# AirU_v2_2.net
KiCad netlist of a schematic drawn in EAGLE
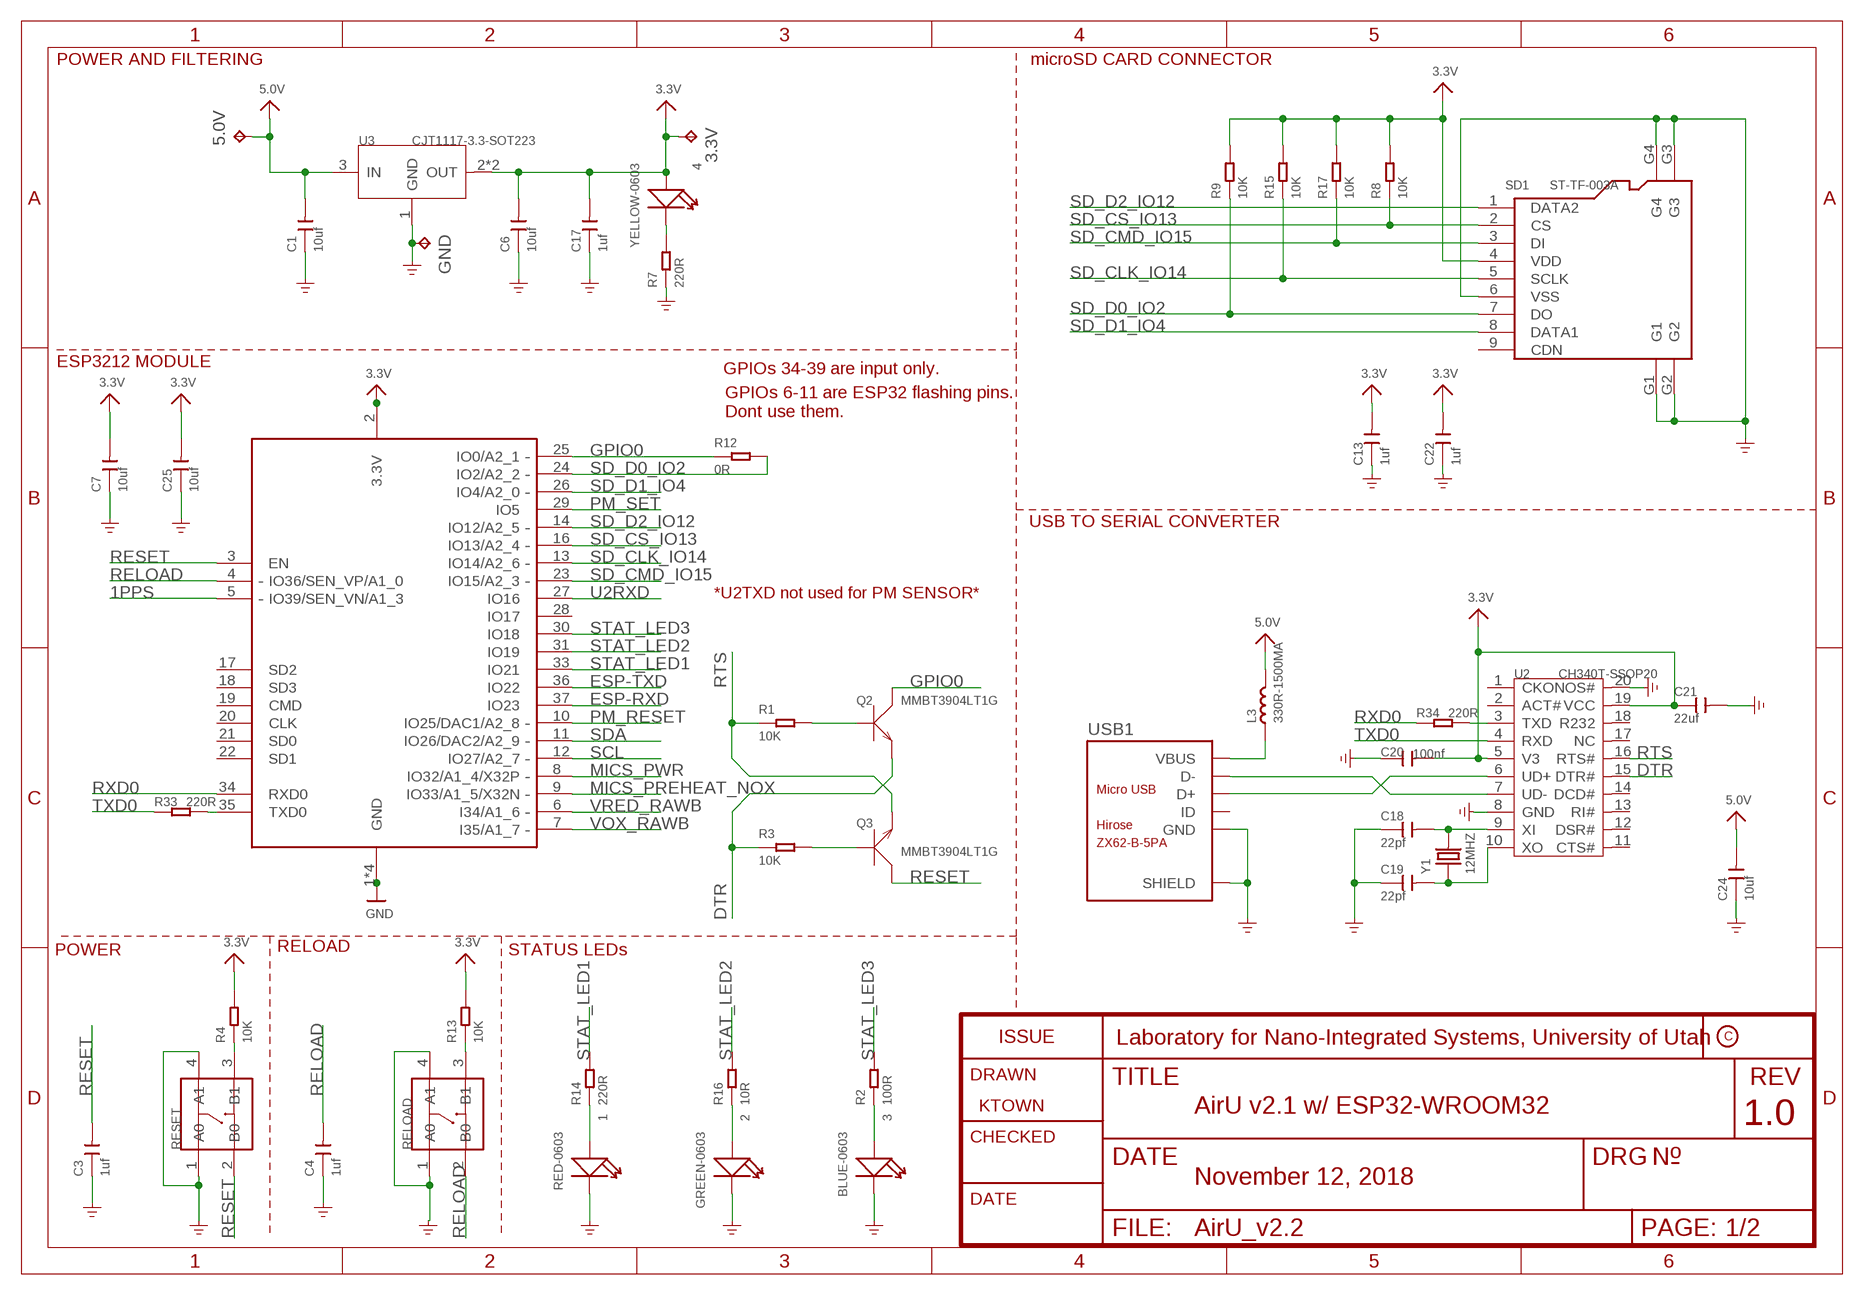
[diagram p0: schematic, sheet 1]
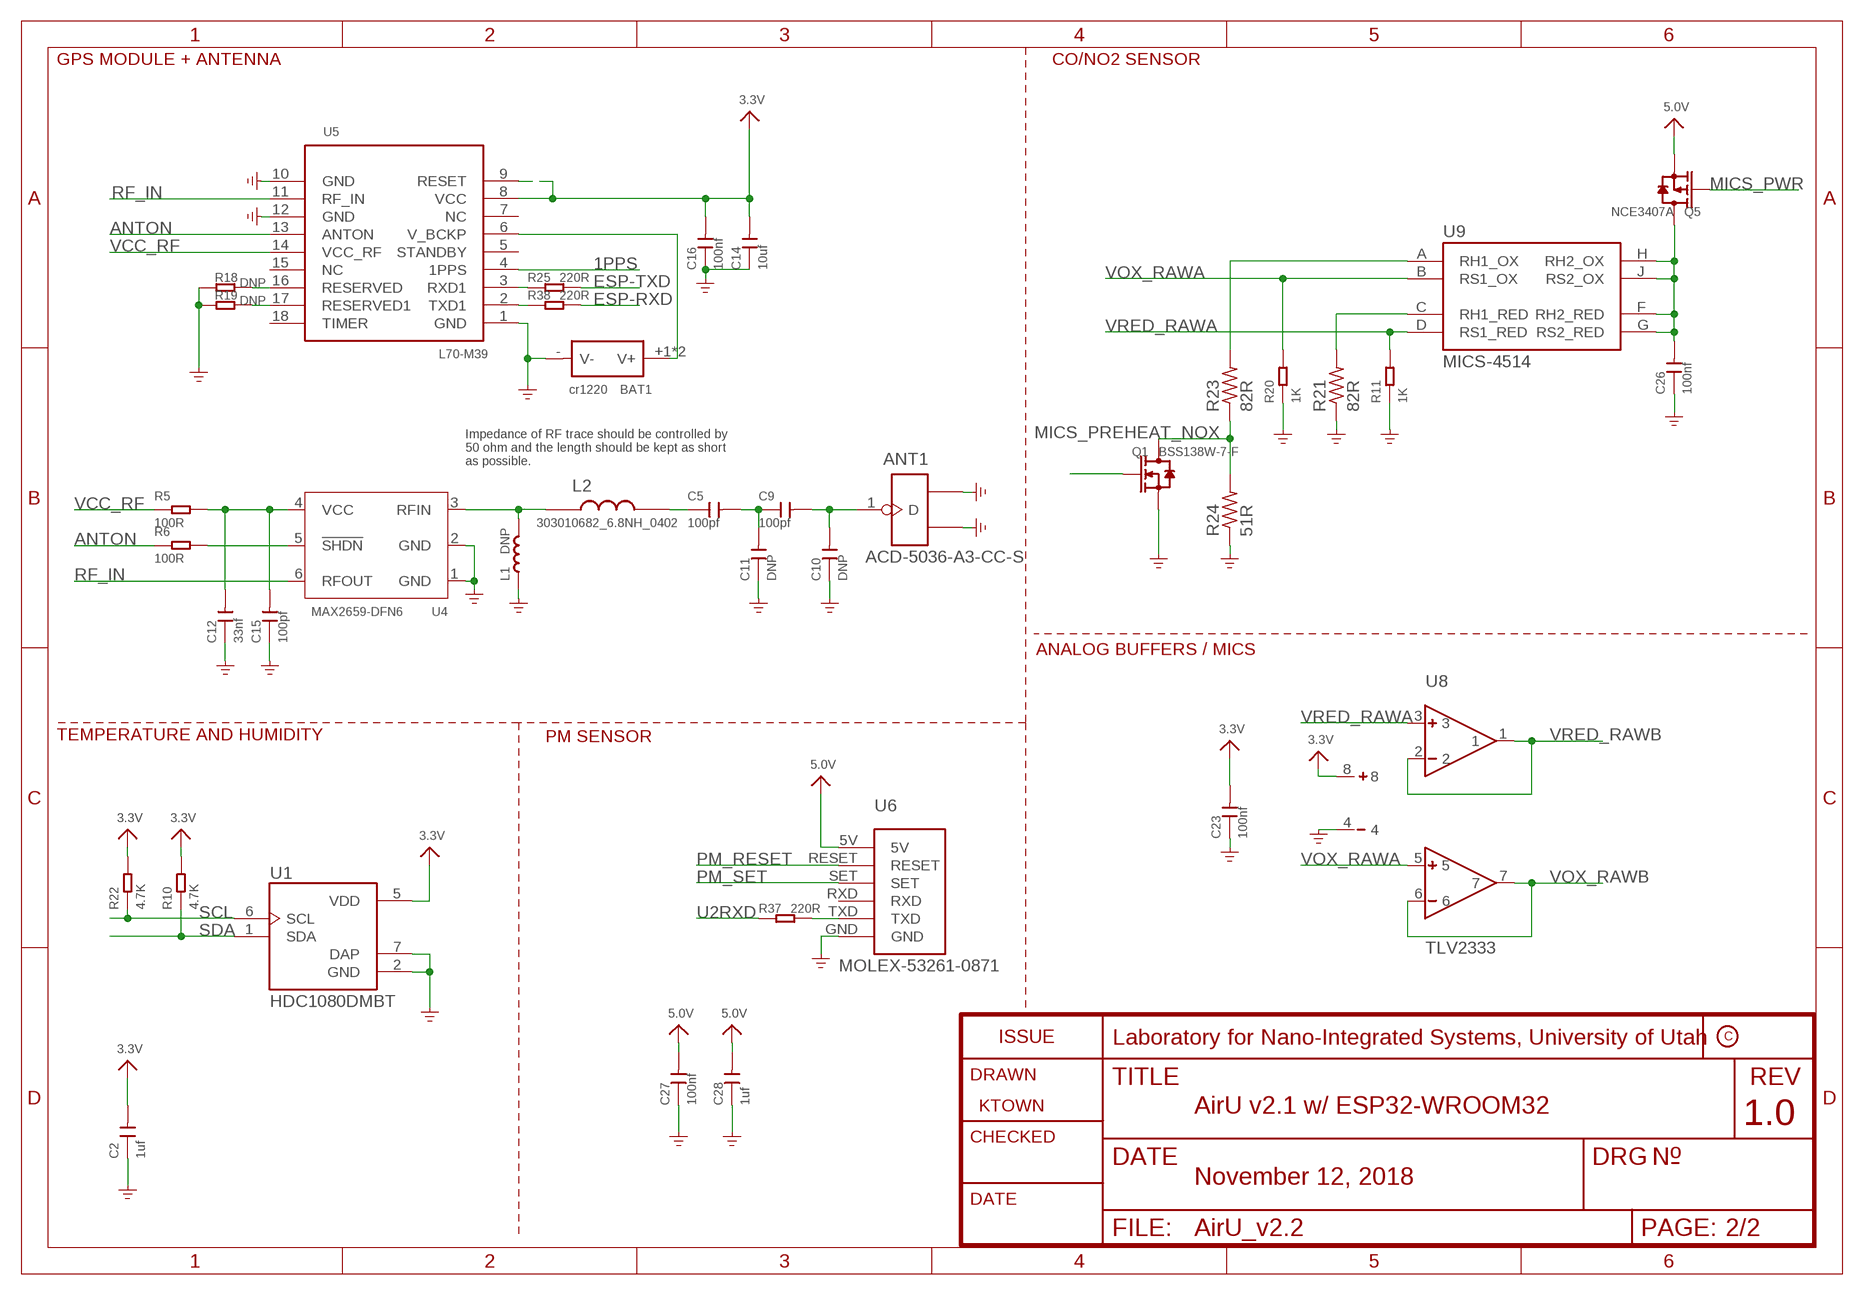
[diagram p1: schematic, sheet 2]

(export (version "E")
  (design (tool "Eeschema 10.0.6"))
  (components
    (comp (ref "1")
      (value "RED-0603")
      (footprint "eagle-import:LED-0603")
      (fields (field (name "MPN") "19-217-R6C-AL1M2VY-3T"))
      (libsource (lib "eagle-import") (part "LED-SMD-RED-DIFFUSED(0603)"))
    )
    (comp (ref "2")
      (value "GREEN-0603")
      (footprint "eagle-import:LED-0603")
      (fields (field (name "MPN") "19-217-G7C-AN1P2-3T"))
      (libsource (lib "eagle-import") (part "SMD-LED-CLEAR-GREEN(0603)"))
    )
    (comp (ref "3")
      (value "BLUE-0603")
      (footprint "eagle-import:LED-0603")
      (fields (field (name "MPN") "19-217-BHC-ZL1M2RY-3T"))
      (libsource (lib "eagle-import") (part "SMD-LED-CLEAR-BLUE(0603)"))
    )
    (comp (ref "3.3V")
      (value "TPTP20SQ")
      (footprint "eagle-import:TP20SQ")
      (libsource (lib "eagle-import") (part "TPTP20SQ"))
    )
    (comp (ref "4")
      (value "YELLOW-0603")
      (footprint "eagle-import:LED-0603")
      (fields (field (name "MPN") "19-217-Y5C-AM1N1VY-3T"))
      (libsource (lib "eagle-import") (part "SMD-LED-CLEAR-YELLOW(0603)"))
    )
    (comp (ref "5.0V")
      (value "TPTP20SQ")
      (footprint "eagle-import:TP20SQ")
      (libsource (lib "eagle-import") (part "TPTP20SQ"))
    )
    (comp (ref "C1")
      (value "10uf")
      (footprint "eagle-import:C0603")
      (fields (field (name "MPN") "CC0603KRX5R6BB106"))
      (libsource (lib "eagle-import") (part "CERAMIC-10UF-10V-10%-X5R(0603)"))
    )
    (comp (ref "C3")
      (value "1uf")
      (footprint "eagle-import:C0603")
      (fields (field (name "MPN") "CC0603KRX7R8BB105"))
      (libsource (lib "eagle-import") (part "CERAMIC-1UF-25V-10%-X7R(0603)"))
    )
    (comp (ref "C4")
      (value "1uf")
      (footprint "eagle-import:C0603")
      (fields (field (name "MPN") "CC0603KRX7R8BB105"))
      (libsource (lib "eagle-import") (part "CERAMIC-1UF-25V-10%-X7R(0603)"))
    )
    (comp (ref "C6")
      (value "10uf")
      (footprint "eagle-import:C0603")
      (fields (field (name "MPN") "CC0603KRX5R6BB106"))
      (libsource (lib "eagle-import") (part "CERAMIC-10UF-10V-10%-X5R(0603)"))
    )
    (comp (ref "C7")
      (value "10uf")
      (footprint "eagle-import:C0603")
      (fields (field (name "MPN") "CC0603KRX5R6BB106"))
      (libsource (lib "eagle-import") (part "CERAMIC-10UF-10V-10%-X5R(0603)"))
    )
    (comp (ref "C13")
      (value "1uf")
      (footprint "eagle-import:C0603")
      (fields (field (name "MPN") "CC0603KRX7R8BB105"))
      (libsource (lib "eagle-import") (part "CERAMIC-1UF-25V-10%-X7R(0603)"))
    )
    (comp (ref "C17")
      (value "1uf")
      (footprint "eagle-import:C0603")
      (fields (field (name "MPN") "CC0603KRX7R8BB105"))
      (libsource (lib "eagle-import") (part "CERAMIC-1UF-25V-10%-X7R(0603)"))
    )
    (comp (ref "C18")
      (value "22pf")
      (footprint "eagle-import:C0603")
      (fields (field (name "MPN") "CC0603JRNPO9BN220"))
      (libsource (lib "eagle-import") (part "CERAMIC-22PF-50V-5%-NPO(0603)"))
    )
    (comp (ref "C19")
      (value "22pf")
      (footprint "eagle-import:C0603")
      (fields (field (name "MPN") "CC0603JRNPO9BN220"))
      (libsource (lib "eagle-import") (part "CERAMIC-22PF-50V-5%-NPO(0603)"))
    )
    (comp (ref "C20")
      (value "100nf")
      (footprint "eagle-import:C0603")
      (fields (field (name "MPN") "CC0603KRX7R9BB104"))
      (libsource (lib "eagle-import") (part "CERAMIC-100NF-50V-10%-X7R(0603)"))
    )
    (comp (ref "C21")
      (value "22uf")
      (footprint "eagle-import:C0805")
      (fields (field (name "MPN") "CC0805MKX5R5BB226"))
      (libsource (lib "eagle-import") (part "CERAMIC-22UF-6.3V-20%-X5R(0805)"))
    )
    (comp (ref "C22")
      (value "1uf")
      (footprint "eagle-import:C0603")
      (fields (field (name "MPN") "CC0603KRX7R8BB105"))
      (libsource (lib "eagle-import") (part "CERAMIC-1UF-25V-10%-X7R(0603)"))
    )
    (comp (ref "C24")
      (value "10uf")
      (footprint "eagle-import:C0603")
      (fields (field (name "MPN") "CC0603KRX5R6BB106"))
      (libsource (lib "eagle-import") (part "CERAMIC-10UF-10V-10%-X5R(0603)"))
    )
    (comp (ref "C25")
      (value "10uf")
      (footprint "eagle-import:C0603")
      (fields (field (name "MPN") "CC0603KRX5R6BB106"))
      (libsource (lib "eagle-import") (part "CERAMIC-10UF-10V-10%-X5R(0603)"))
    )
    (comp (ref "GND")
      (value "TPTP20SQ")
      (footprint "eagle-import:TP20SQ")
      (libsource (lib "eagle-import") (part "TPTP20SQ"))
    )
    (comp (ref "L3")
      (value "330R-1500MA")
      (footprint "eagle-import:L0805")
      (fields (field (name "MPN") "BLM21PG331SN1D"))
      (libsource (lib "eagle-import") (part "SMD-FERRITE-BEAD-330R-1500MA(0805)'0805'"))
    )
    (comp (ref "Q2")
      (value "MMBT3904LT1G")
      (footprint "eagle-import:SOT-23")
      (libsource (lib "eagle-import") (part "SMD-TRANSISTORS-NPN-40V-200MA-MMBT3904LT1G(SOT-23)"))
    )
    (comp (ref "Q3")
      (value "MMBT3904LT1G")
      (footprint "eagle-import:SOT-23")
      (libsource (lib "eagle-import") (part "SMD-TRANSISTORS-NPN-40V-200MA-MMBT3904LT1G(SOT-23)"))
    )
    (comp (ref "R1")
      (value "10K")
      (footprint "eagle-import:R0603")
      (fields (field (name "MPN") "RC0603FR-0710KL"))
      (libsource (lib "eagle-import") (part "SMD-RES-10K-1%-1/10W(0603)"))
    )
    (comp (ref "R2")
      (value "100R")
      (footprint "eagle-import:R0603")
      (fields (field (name "MPN") "RC0603JR-07100RL"))
      (libsource (lib "eagle-import") (part "SMD-RES-100R-5%-1/10W(0603)"))
    )
    (comp (ref "R3")
      (value "10K")
      (footprint "eagle-import:R0603")
      (fields (field (name "MPN") "RC0603FR-0710KL"))
      (libsource (lib "eagle-import") (part "SMD-RES-10K-1%-1/10W(0603)"))
    )
    (comp (ref "R4")
      (value "10K")
      (footprint "eagle-import:R0603")
      (fields (field (name "MPN") "RC0603FR-0710KL"))
      (libsource (lib "eagle-import") (part "SMD-RES-10K-1%-1/10W(0603)"))
    )
    (comp (ref "R7")
      (value "220R")
      (footprint "eagle-import:R0603")
      (fields (field (name "MPN") "RC0603JR-07220RL"))
      (libsource (lib "eagle-import") (part "SMD-RES-220R-5%-1/10W(0603)"))
    )
    (comp (ref "R8")
      (value "10K")
      (footprint "eagle-import:R0603")
      (fields (field (name "MPN") "RC0603FR-0710KL"))
      (libsource (lib "eagle-import") (part "SMD-RES-10K-1%-1/10W(0603)"))
    )
    (comp (ref "R9")
      (value "10K")
      (footprint "eagle-import:R0603")
      (fields (field (name "MPN") "RC0603FR-0710KL"))
      (libsource (lib "eagle-import") (part "SMD-RES-10K-1%-1/10W(0603)"))
    )
    (comp (ref "R12")
      (value "0R")
      (footprint "eagle-import:R0603")
      (fields (field (name "MPN") "RC0603JR-070RL"))
      (libsource (lib "eagle-import") (part "SMD-RES-0R-5%-1/10W(0603)"))
    )
    (comp (ref "R13")
      (value "10K")
      (footprint "eagle-import:R0603")
      (fields (field (name "MPN") "RC0603FR-0710KL"))
      (libsource (lib "eagle-import") (part "SMD-RES-10K-1%-1/10W(0603)"))
    )
    (comp (ref "R14")
      (value "220R")
      (footprint "eagle-import:R0603")
      (fields (field (name "MPN") "RC0603JR-07220RL"))
      (libsource (lib "eagle-import") (part "SMD-RES-220R-5%-1/10W(0603)"))
    )
    (comp (ref "R15")
      (value "10K")
      (footprint "eagle-import:R0603")
      (fields (field (name "MPN") "RC0603FR-0710KL"))
      (libsource (lib "eagle-import") (part "SMD-RES-10K-1%-1/10W(0603)"))
    )
    (comp (ref "R16")
      (value "10R")
      (footprint "eagle-import:R0603")
      (fields (field (name "MPN") "RC0603JR-0710RL"))
      (libsource (lib "eagle-import") (part "SMD-RES-10R-5%-1/10W(0603)"))
    )
    (comp (ref "R17")
      (value "10K")
      (footprint "eagle-import:R0603")
      (fields (field (name "MPN") "RC0603FR-0710KL"))
      (libsource (lib "eagle-import") (part "SMD-RES-10K-1%-1/10W(0603)"))
    )
    (comp (ref "R33")
      (value "220R")
      (footprint "eagle-import:R0603")
      (fields (field (name "MPN") "RC0603JR-07220RL"))
      (libsource (lib "eagle-import") (part "SMD-RES-220R-5%-1/10W(0603)"))
    )
    (comp (ref "R34")
      (value "220R")
      (footprint "eagle-import:R0603")
      (fields (field (name "MPN") "RC0603JR-07220RL"))
      (libsource (lib "eagle-import") (part "SMD-RES-220R-5%-1/10W(0603)"))
    )
    (comp (ref "RELOAD")
      (value "DIP-SWITCH-TACTILE-SPST-NO/TS-1109(4P-D6.0MM)'TS-1109'")
      (footprint "eagle-import:SW4-6.0X6.0X5.0MM")
      (libsource (lib "eagle-import") (part "DIP-SWITCH-TACTILE-SPST-NO/TS-1109(4P-D6.0MM)'TS-1109'"))
    )
    (comp (ref "RESET")
      (value "DIP-SWITCH-TACTILE-SPST-NO/TS-1109(4P-D6.0MM)'TS-1109'")
      (footprint "eagle-import:SW4-6.0X6.0X5.0MM")
      (libsource (lib "eagle-import") (part "DIP-SWITCH-TACTILE-SPST-NO/TS-1109(4P-D6.0MM)'TS-1109'"))
    )
    (comp (ref "SD1")
      (value "ST-TF-003A")
      (footprint "eagle-import:MICRO-SD9+4P-SMD-16.1X14.5X1.85MM")
      (libsource (lib "eagle-import") (part "MICRO-SD-CARD-SOCKET-9P(ST-TF-003A)"))
    )
    (comp (ref "U2")
      (value "CH340T-SSOP20")
      (footprint "eagle-import:SSOP20-0.65-7.6X5.2MM")
      (fields (field (name "MPN") "CH340T"))
      (libsource (lib "eagle-import") (part "INTERFACE-CH340T(SSOP20)"))
    )
    (comp (ref "U3")
      (value "CJT1117-3.3-SOT223")
      (footprint "eagle-import:SOT-223")
      (fields (field (name "MPN") "CJT1117-3.3"))
      (libsource (lib "eagle-import") (part "PMIC-CJT1117-3.3(SOT223)"))
    )
    (comp (ref "U7")
      (value "ESP32_WROOM32_SKINNY")
      (footprint "eagle-import:WROOM32_SKINNY")
      (libsource (lib "eagle-import") (part "ESP32_WROOM32_SKINNY"))
    )
    (comp (ref "USB1")
      (value "ZX62-B-5PA")
      (footprint "eagle-import:MICRO-USB5+6P-SMD-0.65-AB")
      (libsource (lib "eagle-import") (part "MICRO-USB-SMD(ZX62-B-5PA)"))
    )
    (comp (ref "Y1")
      (value "12MHZ")
      (footprint "eagle-import:X2-SMD-5.0X3.2X1.3MM")
      (fields (field (name "MPN") "5032/2P"))
      (libsource (lib "eagle-import") (part "SMD-CRYSTAL-12MHZ-20PF-20PPM-40R(2P-5.0X3.2MM)"))
    )
    (comp (ref "ANT1")
      (value "ACD-5036-A3-CC-S")
      (footprint "eagle-import:ANT3-SMD-5.2X3.7X0.7MM")
      (libsource (lib "eagle-import") (part "ANTENNA-ACD5036"))
    )
    (comp (ref "BAT1")
      (value "cr1220")
      (footprint "eagle-import:BAT2P-13.5-CR1220")
      (libsource (lib "eagle-import") (part "DIP-BATTERY-CELL-HOLDER(1220)"))
    )
    (comp (ref "C2")
      (value "1uf")
      (footprint "eagle-import:C0603")
      (fields (field (name "MPN") "CC0603KRX7R8BB105"))
      (libsource (lib "eagle-import") (part "CERAMIC-1UF-25V-10%-X7R(0603)"))
    )
    (comp (ref "C5")
      (value "100pf")
      (footprint "eagle-import:C0603")
      (fields (field (name "MPN") "CC0603JRNPO9BN101"))
      (libsource (lib "eagle-import") (part "CERAMIC-100PF-50V-5%-NPO(0603)"))
    )
    (comp (ref "C9")
      (value "100pf")
      (footprint "eagle-import:C0603")
      (fields (field (name "MPN") "CC0603JRNPO9BN101"))
      (libsource (lib "eagle-import") (part "CERAMIC-100PF-50V-5%-NPO(0603)"))
    )
    (comp (ref "C10")
      (value "DNP")
      (footprint "eagle-import:C0603")
      (fields (field (name "MPN") "CC0603JRNPO9BN101"))
      (libsource (lib "eagle-import") (part "CERAMIC-100PF-50V-5%-NPO(0603)"))
    )
    (comp (ref "C11")
      (value "DNP")
      (footprint "eagle-import:C0603")
      (fields (field (name "MPN") "CC0603JRNPO9BN101"))
      (libsource (lib "eagle-import") (part "CERAMIC-100PF-50V-5%-NPO(0603)"))
    )
    (comp (ref "C12")
      (value "33nf")
      (footprint "eagle-import:C0603")
      (fields (field (name "MPN") "CC0603KRX7R9BB333"))
      (libsource (lib "eagle-import") (part "CERAMIC-33NF-50V-10%-X7R(0603)"))
    )
    (comp (ref "C14")
      (value "10uf")
      (footprint "eagle-import:C0603")
      (fields (field (name "MPN") "CC0603KRX5R6BB106"))
      (libsource (lib "eagle-import") (part "CERAMIC-10UF-10V-10%-X5R(0603)"))
    )
    (comp (ref "C15")
      (value "100pf")
      (footprint "eagle-import:C0603")
      (fields (field (name "MPN") "CC0603JRNPO9BN101"))
      (libsource (lib "eagle-import") (part "CERAMIC-100PF-50V-5%-NPO(0603)"))
    )
    (comp (ref "C16")
      (value "100nf")
      (footprint "eagle-import:C0603")
      (fields (field (name "MPN") "CC0603KRX7R9BB104"))
      (libsource (lib "eagle-import") (part "CERAMIC-100NF-50V-10%-X7R(0603)"))
    )
    (comp (ref "C23")
      (value "100nf")
      (footprint "eagle-import:C0603")
      (fields (field (name "MPN") "CC0603KRX7R9BB104"))
      (libsource (lib "eagle-import") (part "CERAMIC-100NF-50V-10%-X7R(0603)"))
    )
    (comp (ref "C26")
      (value "100nf")
      (footprint "eagle-import:C0603")
      (fields (field (name "MPN") "CC0603KRX7R9BB104"))
      (libsource (lib "eagle-import") (part "CERAMIC-100NF-50V-10%-X7R(0603)"))
    )
    (comp (ref "C27")
      (value "100nf")
      (footprint "eagle-import:C0603")
      (fields (field (name "MPN") "CC0603KRX7R9BB104"))
      (libsource (lib "eagle-import") (part "CERAMIC-100NF-50V-10%-X7R(0603)"))
    )
    (comp (ref "C28")
      (value "1uf")
      (footprint "eagle-import:C0603")
      (fields (field (name "MPN") "CC0603KRX7R8BB105"))
      (libsource (lib "eagle-import") (part "CERAMIC-1UF-25V-10%-X7R(0603)"))
    )
    (comp (ref "L1")
      (value "DNP")
      (footprint "eagle-import:L0201")
      (libsource (lib "eagle-import") (part "INDUCTOR/FERRITE-BEAD-0201"))
    )
    (comp (ref "L2")
      (value "303010682_6.8NH_0402")
      (footprint "eagle-import:L0402")
      (libsource (lib "eagle-import") (part "303010682_6.8NH_0402"))
    )
    (comp (ref "Q1")
      (value "BSS138W-7-F")
      (footprint "eagle-import:SOT-23")
      (libsource (lib "eagle-import") (part "SMD-MOSFET-N-CH-50V-200MA-BSS138W-7-F(SOT-23)"))
    )
    (comp (ref "Q5")
      (value "NCE3407A")
      (footprint "eagle-import:SOT-23")
      (libsource (lib "eagle-import") (part "SMD-MOSFET-P-CH-VDC=30V-ID=4.3A-NCE3407A(SOT-23)"))
    )
    (comp (ref "R5")
      (value "100R")
      (footprint "eagle-import:R0603")
      (fields (field (name "MPN") "RC0603JR-07100RL"))
      (libsource (lib "eagle-import") (part "SMD-RES-100R-5%-1/10W(0603)"))
    )
    (comp (ref "R6")
      (value "100R")
      (footprint "eagle-import:R0603")
      (fields (field (name "MPN") "RC0603JR-07100RL"))
      (libsource (lib "eagle-import") (part "SMD-RES-100R-5%-1/10W(0603)"))
    )
    (comp (ref "R10")
      (value "4.7K")
      (footprint "eagle-import:R0603")
      (fields (field (name "MPN") "RC0603JR-074K7L"))
      (libsource (lib "eagle-import") (part "SMD-RES-4.7K-5%-1/10W(0603)"))
    )
    (comp (ref "R11")
      (value "1K")
      (footprint "eagle-import:R0603")
      (fields (field (name "MPN") "RC0603FR-071KL"))
      (libsource (lib "eagle-import") (part "SMD-RES-1K-1%-1/10W(0603)"))
    )
    (comp (ref "R18")
      (value "DNP")
      (footprint "eagle-import:R0603")
      (fields (field (name "MPN") "RC0603FR-0710KL"))
      (libsource (lib "eagle-import") (part "SMD-RES-10K-1%-1/10W(0603)"))
    )
    (comp (ref "R19")
      (value "DNP")
      (footprint "eagle-import:R0603")
      (fields (field (name "MPN") "RC0603FR-0710KL"))
      (libsource (lib "eagle-import") (part "SMD-RES-10K-1%-1/10W(0603)"))
    )
    (comp (ref "R20")
      (value "1K")
      (footprint "eagle-import:R0603")
      (fields (field (name "MPN") "RC0603FR-071KL"))
      (libsource (lib "eagle-import") (part "SMD-RES-1K-1%-1/10W(0603)"))
    )
    (comp (ref "R21")
      (value "82R")
      (footprint "eagle-import:R0603")
      (libsource (lib "eagle-import") (part "R-US_R0603"))
    )
    (comp (ref "R22")
      (value "4.7K")
      (footprint "eagle-import:R0603")
      (fields (field (name "MPN") "RC0603JR-074K7L"))
      (libsource (lib "eagle-import") (part "SMD-RES-4.7K-5%-1/10W(0603)"))
    )
    (comp (ref "R23")
      (value "82R")
      (footprint "eagle-import:R0603")
      (libsource (lib "eagle-import") (part "R-US_R0603"))
    )
    (comp (ref "R24")
      (value "51R")
      (footprint "eagle-import:R0603")
      (libsource (lib "eagle-import") (part "R-US_R0603"))
    )
    (comp (ref "R25")
      (value "220R")
      (footprint "eagle-import:R0603")
      (fields (field (name "MPN") "RC0603JR-07220RL"))
      (libsource (lib "eagle-import") (part "SMD-RES-220R-5%-1/10W(0603)"))
    )
    (comp (ref "R37")
      (value "220R")
      (footprint "eagle-import:R0603")
      (fields (field (name "MPN") "RC0603JR-07220RL"))
      (libsource (lib "eagle-import") (part "SMD-RES-220R-5%-1/10W(0603)"))
    )
    (comp (ref "R38")
      (value "220R")
      (footprint "eagle-import:R0603")
      (fields (field (name "MPN") "RC0603JR-07220RL"))
      (libsource (lib "eagle-import") (part "SMD-RES-220R-5%-1/10W(0603)"))
    )
    (comp (ref "U1")
      (value "HDC1080DMBT")
      (footprint "eagle-import:SON100P300X300X80-7N")
      (fields (field (name "DIGI-KEY_PART_NUMBER") "296-43864-1-ND") (field (name "MF") "Texas Instruments"))
      (libsource (lib "eagle-import") (part "HDC1080DMBT"))
    )
    (comp (ref "U4")
      (value "MAX2659-DFN6")
      (footprint "eagle-import:DFN6-0.5-1.5X1.2X0.72MM")
      (fields (field (name "MPN") "MAX2659"))
      (libsource (lib "eagle-import") (part "AMPLIFIER-MAX2659"))
    )
    (comp (ref "U5")
      (value "L70-M39")
      (footprint "eagle-import:LGA18-1.1-9.7X10.1X2.5MM")
      (fields (field (name "MPN") "L70"))
      (libsource (lib "eagle-import") (part "MOUDLE-GPS-L70-HARDWARE"))
    )
    (comp (ref "U6")
      (value "MOLEX-53261-0871")
      (footprint "eagle-import:MOLEX-53261-0871")
      (libsource (lib "eagle-import") (part "MOLEX-53261-0871"))
    )
    (comp (ref "U8")
      (value "TLV2333")
      (footprint "eagle-import:TLV2333")
      (libsource (lib "eagle-import") (part "TLV2333"))
    )
    (comp (ref "U9")
      (value "MICS-4514")
      (footprint "eagle-import:MICS_10-SMD")
      (fields (field (name "MF") "Amphenol"))
      (libsource (lib "eagle-import") (part "MICS-4514"))
    )
  )
  (nets
    (net (code "1") (name "1PPS") (class "Default")
      (node (ref "U5") (pin "4") (pinfunction "1PPS_4") (pintype "bidirectional"))
      (node (ref "U7") (pin "5") (pinfunction "IO39/SEN_VN/A1_3_5") (pintype "passive"))
    )
    (net (code "2") (name "3.3V") (class "Default")
      (node (ref "3.3V") (pin "TP") (pinfunction "TP_TP") (pintype "input"))
      (node (ref "4") (pin "+") (pinfunction "+_+") (pintype "passive"))
      (node (ref "C13") (pin "2") (pinfunction "2_2") (pintype "passive"))
      (node (ref "C14") (pin "2") (pinfunction "2_2") (pintype "passive"))
      (node (ref "C16") (pin "2") (pinfunction "2_2") (pintype "passive"))
      (node (ref "C17") (pin "2") (pinfunction "2_2") (pintype "passive"))
      (node (ref "C2") (pin "2") (pinfunction "2_2") (pintype "passive"))
      (node (ref "C20") (pin "2") (pinfunction "2_2") (pintype "passive"))
      (node (ref "C21") (pin "1") (pinfunction "1_1") (pintype "passive"))
      (node (ref "C22") (pin "2") (pinfunction "2_2") (pintype "passive"))
      (node (ref "C23") (pin "2") (pinfunction "2_2") (pintype "passive"))
      (node (ref "C25") (pin "2") (pinfunction "2_2") (pintype "passive"))
      (node (ref "C6") (pin "2") (pinfunction "2_2") (pintype "passive"))
      (node (ref "C7") (pin "2") (pinfunction "2_2") (pintype "passive"))
      (node (ref "R10") (pin "2") (pinfunction "2_2") (pintype "passive"))
      (node (ref "R13") (pin "2") (pinfunction "2_2") (pintype "passive"))
      (node (ref "R15") (pin "2") (pinfunction "2_2") (pintype "passive"))
      (node (ref "R17") (pin "2") (pinfunction "2_2") (pintype "passive"))
      (node (ref "R22") (pin "2") (pinfunction "2_2") (pintype "passive"))
      (node (ref "R4") (pin "2") (pinfunction "2_2") (pintype "passive"))
      (node (ref "R8") (pin "2") (pinfunction "2_2") (pintype "passive"))
      (node (ref "R9") (pin "2") (pinfunction "2_2") (pintype "passive"))
      (node (ref "SD1") (pin "4") (pinfunction "VDD_4") (pintype "bidirectional"))
      (node (ref "U1") (pin "5") (pinfunction "VDD_5") (pintype "power_in"))
      (node (ref "U2") (pin "19") (pinfunction "VCC_19") (pintype "power_in"))
      (node (ref "U2") (pin "5") (pinfunction "V3_5") (pintype "power_in"))
      (node (ref "U3") (pin "2") (pinfunction "OUT_2") (pintype "bidirectional"))
      (node (ref "U3") (pin "TER") (pinfunction "OUT_TER") (pintype "bidirectional"))
      (node (ref "U5") (pin "8") (pinfunction "VCC_8") (pintype "power_in"))
      (node (ref "U5") (pin "9") (pinfunction "RESET_9") (pintype "bidirectional"))
      (node (ref "U7") (pin "2") (pinfunction "3.3V_2") (pintype "passive"))
      (node (ref "U8") (pin "8") (pinfunction "8_8") (pintype "bidirectional"))
    )
    (net (code "3") (name "5.0V") (class "Default")
      (node (ref "5.0V") (pin "TP") (pinfunction "TP_TP") (pintype "input"))
      (node (ref "C1") (pin "2") (pinfunction "2_2") (pintype "passive"))
      (node (ref "C24") (pin "2") (pinfunction "2_2") (pintype "passive"))
      (node (ref "C27") (pin "2") (pinfunction "2_2") (pintype "passive"))
      (node (ref "C28") (pin "2") (pinfunction "2_2") (pintype "passive"))
      (node (ref "L3") (pin "2") (pinfunction "2_2") (pintype "passive"))
      (node (ref "Q5") (pin "2") (pinfunction "S_2") (pintype "passive"))
      (node (ref "U3") (pin "3") (pinfunction "IN_3") (pintype "bidirectional"))
      (node (ref "U6") (pin "5V") (pinfunction "5V_5V") (pintype "bidirectional"))
    )
    (net (code "4") (name "ANTON") (class "Default")
      (node (ref "R6") (pin "1") (pinfunction "1_1") (pintype "passive"))
      (node (ref "U5") (pin "13") (pinfunction "ANTON_13") (pintype "bidirectional"))
    )
    (net (code "5") (name "DTR") (class "Default")
      (node (ref "Q2") (pin "2") (pinfunction "E_2") (pintype "passive"))
      (node (ref "R3") (pin "1") (pinfunction "1_1") (pintype "passive"))
      (node (ref "U2") (pin "15") (pinfunction "DTR#_15") (pintype "output"))
    )
    (net (code "6") (name "ESP-RXD") (class "Default")
      (node (ref "R38") (pin "2") (pinfunction "2_2") (pintype "passive"))
      (node (ref "U7") (pin "37") (pinfunction "IO23_37") (pintype "bidirectional"))
    )
    (net (code "7") (name "ESP-TXD") (class "Default")
      (node (ref "R25") (pin "2") (pinfunction "2_2") (pintype "passive"))
      (node (ref "U7") (pin "36") (pinfunction "IO22_36") (pintype "bidirectional"))
    )
    (net (code "8") (name "GND") (class "Default")
      (node (ref "1") (pin "-") (pinfunction "-_-") (pintype "passive"))
      (node (ref "2") (pin "-") (pinfunction "-_-") (pintype "passive"))
      (node (ref "3") (pin "-") (pinfunction "-_-") (pintype "passive"))
      (node (ref "ANT1") (pin "2") (pinfunction "GND1_2") (pintype "bidirectional"))
      (node (ref "ANT1") (pin "3") (pinfunction "GND2_3") (pintype "bidirectional"))
      (node (ref "BAT1") (pin "-") (pinfunction "V-_-") (pintype "bidirectional"))
      (node (ref "C1") (pin "1") (pinfunction "1_1") (pintype "passive"))
      (node (ref "C10") (pin "1") (pinfunction "1_1") (pintype "passive"))
      (node (ref "C11") (pin "1") (pinfunction "1_1") (pintype "passive"))
      (node (ref "C12") (pin "1") (pinfunction "1_1") (pintype "passive"))
      (node (ref "C13") (pin "1") (pinfunction "1_1") (pintype "passive"))
      (node (ref "C14") (pin "1") (pinfunction "1_1") (pintype "passive"))
      (node (ref "C15") (pin "1") (pinfunction "1_1") (pintype "passive"))
      (node (ref "C16") (pin "1") (pinfunction "1_1") (pintype "passive"))
      (node (ref "C17") (pin "1") (pinfunction "1_1") (pintype "passive"))
      (node (ref "C18") (pin "1") (pinfunction "1_1") (pintype "passive"))
      (node (ref "C19") (pin "1") (pinfunction "1_1") (pintype "passive"))
      (node (ref "C2") (pin "1") (pinfunction "1_1") (pintype "passive"))
      (node (ref "C20") (pin "1") (pinfunction "1_1") (pintype "passive"))
      (node (ref "C21") (pin "2") (pinfunction "2_2") (pintype "passive"))
      (node (ref "C22") (pin "1") (pinfunction "1_1") (pintype "passive"))
      (node (ref "C23") (pin "1") (pinfunction "1_1") (pintype "passive"))
      (node (ref "C24") (pin "1") (pinfunction "1_1") (pintype "passive"))
      (node (ref "C25") (pin "1") (pinfunction "1_1") (pintype "passive"))
      (node (ref "C26") (pin "1") (pinfunction "1_1") (pintype "passive"))
      (node (ref "C27") (pin "1") (pinfunction "1_1") (pintype "passive"))
      (node (ref "C28") (pin "1") (pinfunction "1_1") (pintype "passive"))
      (node (ref "C3") (pin "1") (pinfunction "1_1") (pintype "passive"))
      (node (ref "C4") (pin "1") (pinfunction "1_1") (pintype "passive"))
      (node (ref "C6") (pin "1") (pinfunction "1_1") (pintype "passive"))
      (node (ref "C7") (pin "1") (pinfunction "1_1") (pintype "passive"))
      (node (ref "GND") (pin "TP") (pinfunction "TP_TP") (pintype "input"))
      (node (ref "L1") (pin "1") (pinfunction "1_1") (pintype "passive"))
      (node (ref "Q1") (pin "2") (pinfunction "S_2") (pintype "passive"))
      (node (ref "R11") (pin "1") (pinfunction "1_1") (pintype "passive"))
      (node (ref "R18") (pin "1") (pinfunction "1_1") (pintype "passive"))
      (node (ref "R19") (pin "1") (pinfunction "1_1") (pintype "passive"))
      (node (ref "R20") (pin "1") (pinfunction "1_1") (pintype "passive"))
      (node (ref "R21") (pin "1") (pinfunction "1_1") (pintype "passive"))
      (node (ref "R24") (pin "1") (pinfunction "1_1") (pintype "passive"))
      (node (ref "R7") (pin "1") (pinfunction "1_1") (pintype "passive"))
      (node (ref "RELOAD") (pin "1") (pinfunction "A0_1") (pintype "bidirectional"))
      (node (ref "RELOAD") (pin "4") (pinfunction "A1_4") (pintype "bidirectional"))
      (node (ref "RESET") (pin "1") (pinfunction "A0_1") (pintype "bidirectional"))
      (node (ref "RESET") (pin "4") (pinfunction "A1_4") (pintype "bidirectional"))
      (node (ref "SD1") (pin "6") (pinfunction "VSS_6") (pintype "bidirectional"))
      (node (ref "SD1") (pin "G1") (pinfunction "G1_G1") (pintype "bidirectional"))
      (node (ref "SD1") (pin "G2") (pinfunction "G2_G2") (pintype "bidirectional"))
      (node (ref "SD1") (pin "G3") (pinfunction "G3_G3") (pintype "bidirectional"))
      (node (ref "SD1") (pin "G4") (pinfunction "G4_G4") (pintype "bidirectional"))
      (node (ref "U1") (pin "2") (pinfunction "GND_2") (pintype "power_in"))
      (node (ref "U1") (pin "7") (pinfunction "DAP_7") (pintype "power_in"))
      (node (ref "U2") (pin "20") (pinfunction "NOS#_20") (pintype "power_in"))
      (node (ref "U2") (pin "8") (pinfunction "GND_8") (pintype "power_in"))
      (node (ref "U3") (pin "1") (pinfunction "GND_1") (pintype "bidirectional"))
      (node (ref "U4") (pin "1") (pinfunction "GND_1") (pintype "power_in"))
      (node (ref "U4") (pin "2") (pinfunction "GND_2") (pintype "power_in"))
      (node (ref "U5") (pin "1") (pinfunction "GND_1") (pintype "power_in"))
      (node (ref "U5") (pin "10") (pinfunction "GND_10") (pintype "power_in"))
      (node (ref "U5") (pin "12") (pinfunction "GND_12") (pintype "bidirectional"))
      (node (ref "U6") (pin "GND") (pinfunction "GND_GND") (pintype "bidirectional"))
      (node (ref "U7") (pin "1") (pinfunction "GND_1") (pintype "passive"))
      (node (ref "U7") (pin "15") (pinfunction "GND_15") (pintype "passive"))
      (node (ref "U7") (pin "38") (pinfunction "GND_38") (pintype "passive"))
      (node (ref "U7") (pin "P$1") (pinfunction "GND_P$1") (pintype "passive"))
      (node (ref "U8") (pin "4") (pinfunction "4_4") (pintype "bidirectional"))
      (node (ref "USB1") (pin "5") (pinfunction "GND_5") (pintype "power_in"))
      (node (ref "USB1") (pin "P1") (pinfunction "SHIELD_P1") (pintype "power_in"))
      (node (ref "USB1") (pin "P2") (pinfunction "SHIELD_P2") (pintype "power_in"))
      (node (ref "USB1") (pin "P3_1") (pinfunction "SHIELD_P3_1") (pintype "power_in"))
      (node (ref "USB1") (pin "P3_2") (pinfunction "SHIELD_P3_2") (pintype "power_in"))
      (node (ref "USB1") (pin "P3_3") (pinfunction "SHIELD_P3_3") (pintype "power_in"))
      (node (ref "USB1") (pin "P4_1") (pinfunction "SHIELD_P4_1") (pintype "power_in"))
      (node (ref "USB1") (pin "P4_2") (pinfunction "SHIELD_P4_2") (pintype "power_in"))
      (node (ref "USB1") (pin "P4_3") (pinfunction "SHIELD_P4_3") (pintype "power_in"))
      (node (ref "USB1") (pin "P5") (pinfunction "SHIELD_P5") (pintype "power_in"))
      (node (ref "USB1") (pin "P6") (pinfunction "SHIELD_P6") (pintype "power_in"))
    )
    (net (code "9") (name "GPIO0") (class "Default")
      (node (ref "Q2") (pin "3") (pinfunction "C_3") (pintype "passive"))
      (node (ref "R12") (pin "1") (pinfunction "1_1") (pintype "passive"))
      (node (ref "U7") (pin "25") (pinfunction "IO0/A2_1_25") (pintype "bidirectional"))
    )
    (net (code "10") (name "MICS_PREHEAT_NOX") (class "Default")
      (node (ref "Q1") (pin "1") (pinfunction "G_1") (pintype "passive"))
      (node (ref "U7") (pin "9") (pinfunction "IO33/A1_5/X32N_9") (pintype "bidirectional"))
    )
    (net (code "11") (name "MICS_PWR") (class "Default")
      (node (ref "Q5") (pin "1") (pinfunction "G_1") (pintype "passive"))
      (node (ref "U7") (pin "8") (pinfunction "IO32/A1_4/X32P_8") (pintype "bidirectional"))
    )
    (net (code "12") (name "Net-(1-Pad+)") (class "Default")
      (node (ref "1") (pin "+") (pinfunction "+_+") (pintype "passive"))
      (node (ref "R14") (pin "1") (pinfunction "1_1") (pintype "passive"))
    )
    (net (code "13") (name "Net-(2-Pad+)") (class "Default")
      (node (ref "2") (pin "+") (pinfunction "+_+") (pintype "passive"))
      (node (ref "R16") (pin "1") (pinfunction "1_1") (pintype "passive"))
    )
    (net (code "14") (name "Net-(3-Pad+)") (class "Default")
      (node (ref "3") (pin "+") (pinfunction "+_+") (pintype "passive"))
      (node (ref "R2") (pin "1") (pinfunction "1_1") (pintype "passive"))
    )
    (net (code "15") (name "Net-(4-Pad-)") (class "Default")
      (node (ref "4") (pin "-") (pinfunction "-_-") (pintype "passive"))
      (node (ref "R7") (pin "2") (pinfunction "2_2") (pintype "passive"))
    )
    (net (code "16") (name "Net-(ANT1-D)") (class "Default")
      (node (ref "ANT1") (pin "1") (pinfunction "D_1") (pintype "bidirectional"))
      (node (ref "C10") (pin "2") (pinfunction "2_2") (pintype "passive"))
      (node (ref "C9") (pin "2") (pinfunction "2_2") (pintype "passive"))
    )
    (net (code "17") (name "Net-(C5-Pad1)") (class "Default")
      (node (ref "C5") (pin "1") (pinfunction "1_1") (pintype "passive"))
      (node (ref "L2") (pin "P$2") (pinfunction "P$2_P$2") (pintype "passive"))
    )
    (net (code "18") (name "Net-(C11-Pad2)") (class "Default")
      (node (ref "C11") (pin "2") (pinfunction "2_2") (pintype "passive"))
      (node (ref "C5") (pin "2") (pinfunction "2_2") (pintype "passive"))
      (node (ref "C9") (pin "1") (pinfunction "1_1") (pintype "passive"))
    )
    (net (code "19") (name "Net-(Q1-D)") (class "Default")
      (node (ref "Q1") (pin "3") (pinfunction "D_3") (pintype "passive"))
      (node (ref "R23") (pin "1") (pinfunction "1_1") (pintype "passive"))
      (node (ref "R24") (pin "2") (pinfunction "2_2") (pintype "passive"))
    )
    (net (code "20") (name "Net-(Q2-B)") (class "Default")
      (node (ref "Q2") (pin "1") (pinfunction "B_1") (pintype "passive"))
      (node (ref "R1") (pin "2") (pinfunction "2_2") (pintype "passive"))
    )
    (net (code "21") (name "Net-(Q3-B)") (class "Default")
      (node (ref "Q3") (pin "1") (pinfunction "B_1") (pintype "passive"))
      (node (ref "R3") (pin "2") (pinfunction "2_2") (pintype "passive"))
    )
    (net (code "22") (name "Net-(Q5-D)") (class "Default")
      (node (ref "C26") (pin "2") (pinfunction "2_2") (pintype "passive"))
      (node (ref "Q5") (pin "3") (pinfunction "D_3") (pintype "passive"))
      (node (ref "U9") (pin "F") (pinfunction "RH2_RED_F") (pintype "bidirectional"))
      (node (ref "U9") (pin "G") (pinfunction "RS2_RED_G") (pintype "bidirectional"))
      (node (ref "U9") (pin "H") (pinfunction "RH2_OX_H") (pintype "bidirectional"))
      (node (ref "U9") (pin "J") (pinfunction "RS2_OX_J") (pintype "bidirectional"))
    )
    (net (code "23") (name "Net-(R37-Pad2)") (class "Default")
      (node (ref "R37") (pin "2") (pinfunction "2_2") (pintype "passive"))
      (node (ref "U6") (pin "TXD") (pinfunction "TXD_TXD") (pintype "bidirectional"))
    )
    (net (code "24") (name "Net-(RELOAD-B1)") (class "Default")
      (node (ref "R13") (pin "1") (pinfunction "1_1") (pintype "passive"))
      (node (ref "RELOAD") (pin "3") (pinfunction "B1_3") (pintype "bidirectional"))
    )
    (net (code "25") (name "Net-(RESET-B1)") (class "Default")
      (node (ref "R4") (pin "1") (pinfunction "1_1") (pintype "passive"))
      (node (ref "RESET") (pin "3") (pinfunction "B1_3") (pintype "bidirectional"))
    )
    (net (code "26") (name "Net-(U2-TXD)") (class "Default")
      (node (ref "R34") (pin "2") (pinfunction "2_2") (pintype "passive"))
      (node (ref "U2") (pin "3") (pinfunction "TXD_3") (pintype "output"))
    )
    (net (code "27") (name "Net-(U2-UD+)") (class "Default")
      (node (ref "U2") (pin "6") (pinfunction "UD+_6") (pintype "bidirectional"))
      (node (ref "USB1") (pin "3") (pinfunction "D+_3") (pintype "bidirectional"))
    )
    (net (code "28") (name "Net-(U2-UD-)") (class "Default")
      (node (ref "U2") (pin "7") (pinfunction "UD-_7") (pintype "bidirectional"))
      (node (ref "USB1") (pin "2") (pinfunction "D-_2") (pintype "bidirectional"))
    )
    (net (code "29") (name "Net-(U2-XI)") (class "Default")
      (node (ref "C18") (pin "2") (pinfunction "2_2") (pintype "passive"))
      (node (ref "U2") (pin "9") (pinfunction "XI_9") (pintype "input"))
      (node (ref "Y1") (pin "2") (pinfunction "2_2") (pintype "passive"))
    )
    (net (code "30") (name "Net-(U2-XO)") (class "Default")
      (node (ref "C19") (pin "2") (pinfunction "2_2") (pintype "passive"))
      (node (ref "U2") (pin "10") (pinfunction "XO_10") (pintype "output"))
      (node (ref "Y1") (pin "1") (pinfunction "1_1") (pintype "passive"))
    )
    (net (code "31") (name "Net-(U4-RFIN)") (class "Default")
      (node (ref "L1") (pin "2") (pinfunction "2_2") (pintype "passive"))
      (node (ref "L2") (pin "P$1") (pinfunction "P$1_P$1") (pintype "passive"))
      (node (ref "U4") (pin "3") (pinfunction "RFIN_3") (pintype "bidirectional"))
    )
    (net (code "32") (name "Net-(U4-VCC)") (class "Default")
      (node (ref "C12") (pin "2") (pinfunction "2_2") (pintype "passive"))
      (node (ref "C15") (pin "2") (pinfunction "2_2") (pintype "passive"))
      (node (ref "R5") (pin "2") (pinfunction "2_2") (pintype "passive"))
      (node (ref "U4") (pin "4") (pinfunction "VCC_4") (pintype "power_in"))
    )
    (net (code "33") (name "Net-(U4-~{SHDN})") (class "Default")
      (node (ref "R6") (pin "2") (pinfunction "2_2") (pintype "passive"))
      (node (ref "U4") (pin "5") (pinfunction "~{SHDN}_5") (pintype "bidirectional"))
    )
    (net (code "34") (name "Net-(U5-RESERVED)") (class "Default")
      (node (ref "R18") (pin "2") (pinfunction "2_2") (pintype "passive"))
      (node (ref "U5") (pin "16") (pinfunction "RESERVED_16") (pintype "bidirectional"))
    )
    (net (code "35") (name "Net-(U5-RESERVED1)") (class "Default")
      (node (ref "R19") (pin "2") (pinfunction "2_2") (pintype "passive"))
      (node (ref "U5") (pin "17") (pinfunction "RESERVED1_17") (pintype "bidirectional"))
    )
    (net (code "36") (name "Net-(U5-RXD1)") (class "Default")
      (node (ref "R25") (pin "1") (pinfunction "1_1") (pintype "passive"))
      (node (ref "U5") (pin "3") (pinfunction "RXD1_3") (pintype "bidirectional"))
    )
    (net (code "37") (name "Net-(U5-TXD1)") (class "Default")
      (node (ref "R38") (pin "1") (pinfunction "1_1") (pintype "passive"))
      (node (ref "U5") (pin "2") (pinfunction "TXD1_2") (pintype "bidirectional"))
    )
    (net (code "38") (name "Net-(U5-V_BCKP)") (class "Default")
      (node (ref "BAT1") (pin "+1") (pinfunction "V+_+1") (pintype "bidirectional"))
      (node (ref "BAT1") (pin "+2") (pinfunction "V+_+2") (pintype "bidirectional"))
      (node (ref "U5") (pin "6") (pinfunction "V_BCKP_6") (pintype "bidirectional"))
    )
    (net (code "39") (name "Net-(U7-TXD0)") (class "Default")
      (node (ref "R33") (pin "2") (pinfunction "2_2") (pintype "passive"))
      (node (ref "U7") (pin "35") (pinfunction "TXD0_35") (pintype "output"))
    )
    (net (code "40") (name "Net-(U9-RH1_OX)") (class "Default")
      (node (ref "R23") (pin "2") (pinfunction "2_2") (pintype "passive"))
      (node (ref "U9") (pin "A") (pinfunction "RH1_OX_A") (pintype "bidirectional"))
    )
    (net (code "41") (name "Net-(U9-RH1_RED)") (class "Default")
      (node (ref "R21") (pin "2") (pinfunction "2_2") (pintype "passive"))
      (node (ref "U9") (pin "C") (pinfunction "RH1_RED_C") (pintype "bidirectional"))
    )
    (net (code "42") (name "Net-(USB1-VBUS)") (class "Default")
      (node (ref "L3") (pin "1") (pinfunction "1_1") (pintype "passive"))
      (node (ref "USB1") (pin "1") (pinfunction "VBUS_1") (pintype "power_in"))
    )
    (net (code "43") (name "PM_RESET") (class "Default")
      (node (ref "U6") (pin "RESET") (pinfunction "RESET_RESET") (pintype "bidirectional"))
      (node (ref "U7") (pin "10") (pinfunction "IO25/DAC1/A2_8_10") (pintype "bidirectional"))
    )
    (net (code "44") (name "PM_SET") (class "Default")
      (node (ref "U6") (pin "SET") (pinfunction "SET_SET") (pintype "bidirectional"))
      (node (ref "U7") (pin "29") (pinfunction "IO5_29") (pintype "bidirectional"))
    )
    (net (code "45") (name "RELOAD") (class "Default")
      (node (ref "C4") (pin "2") (pinfunction "2_2") (pintype "passive"))
      (node (ref "RELOAD") (pin "2") (pinfunction "B0_2") (pintype "bidirectional"))
      (node (ref "U7") (pin "4") (pinfunction "IO36/SEN_VP/A1_0_4") (pintype "passive"))
    )
    (net (code "46") (name "RESET") (class "Default")
      (node (ref "C3") (pin "2") (pinfunction "2_2") (pintype "passive"))
      (node (ref "Q3") (pin "3") (pinfunction "C_3") (pintype "passive"))
      (node (ref "RESET") (pin "2") (pinfunction "B0_2") (pintype "bidirectional"))
      (node (ref "U7") (pin "3") (pinfunction "EN_3") (pintype "input"))
    )
    (net (code "47") (name "RF_IN") (class "Default")
      (node (ref "U4") (pin "6") (pinfunction "RFOUT_6") (pintype "bidirectional"))
      (node (ref "U5") (pin "11") (pinfunction "RF_IN_11") (pintype "bidirectional"))
    )
    (net (code "48") (name "RTS") (class "Default")
      (node (ref "Q3") (pin "2") (pinfunction "E_2") (pintype "passive"))
      (node (ref "R1") (pin "1") (pinfunction "1_1") (pintype "passive"))
      (node (ref "U2") (pin "16") (pinfunction "RTS#_16") (pintype "output"))
    )
    (net (code "49") (name "RXD0") (class "Default")
      (node (ref "R34") (pin "1") (pinfunction "1_1") (pintype "passive"))
      (node (ref "U7") (pin "34") (pinfunction "RXD0_34") (pintype "input"))
    )
    (net (code "50") (name "SCL") (class "Default")
      (node (ref "R22") (pin "1") (pinfunction "1_1") (pintype "passive"))
      (node (ref "U1") (pin "6") (pinfunction "SCL_6") (pintype "input"))
      (node (ref "U7") (pin "12") (pinfunction "IO27/A2_7_12") (pintype "bidirectional"))
    )
    (net (code "51") (name "SDA") (class "Default")
      (node (ref "R10") (pin "1") (pinfunction "1_1") (pintype "passive"))
      (node (ref "U1") (pin "1") (pinfunction "SDA_1") (pintype "bidirectional"))
      (node (ref "U7") (pin "11") (pinfunction "IO26/DAC2/A2_9_11") (pintype "bidirectional"))
    )
    (net (code "52") (name "SD_CLK_IO14") (class "Default")
      (node (ref "R15") (pin "1") (pinfunction "1_1") (pintype "passive"))
      (node (ref "SD1") (pin "5") (pinfunction "SCLK_5") (pintype "bidirectional"))
      (node (ref "U7") (pin "13") (pinfunction "IO14/A2_6_13") (pintype "bidirectional"))
    )
    (net (code "53") (name "SD_CMD_IO15") (class "Default")
      (node (ref "R17") (pin "1") (pinfunction "1_1") (pintype "passive"))
      (node (ref "SD1") (pin "3") (pinfunction "DI_3") (pintype "bidirectional"))
      (node (ref "U7") (pin "23") (pinfunction "IO15/A2_3_23") (pintype "bidirectional"))
    )
    (net (code "54") (name "SD_CS_IO13") (class "Default")
      (node (ref "R8") (pin "1") (pinfunction "1_1") (pintype "passive"))
      (node (ref "SD1") (pin "2") (pinfunction "CS_2") (pintype "bidirectional"))
      (node (ref "U7") (pin "16") (pinfunction "IO13/A2_4_16") (pintype "bidirectional"))
    )
    (net (code "55") (name "SD_D0_IO2") (class "Default")
      (node (ref "R12") (pin "2") (pinfunction "2_2") (pintype "passive"))
      (node (ref "R9") (pin "1") (pinfunction "1_1") (pintype "passive"))
      (node (ref "SD1") (pin "7") (pinfunction "DO_7") (pintype "bidirectional"))
      (node (ref "U7") (pin "24") (pinfunction "IO2/A2_2_24") (pintype "bidirectional"))
    )
    (net (code "56") (name "SD_D1_IO4") (class "Default")
      (node (ref "SD1") (pin "8") (pinfunction "DATA1_8") (pintype "bidirectional"))
      (node (ref "U7") (pin "26") (pinfunction "IO4/A2_0_26") (pintype "bidirectional"))
    )
    (net (code "57") (name "SD_D2_IO12") (class "Default")
      (node (ref "SD1") (pin "1") (pinfunction "DATA2_1") (pintype "bidirectional"))
      (node (ref "U7") (pin "14") (pinfunction "IO12/A2_5_14") (pintype "bidirectional"))
    )
    (net (code "58") (name "STAT_LED1") (class "Default")
      (node (ref "R14") (pin "2") (pinfunction "2_2") (pintype "passive"))
      (node (ref "U7") (pin "33") (pinfunction "IO21_33") (pintype "bidirectional"))
    )
    (net (code "59") (name "STAT_LED2") (class "Default")
      (node (ref "R16") (pin "2") (pinfunction "2_2") (pintype "passive"))
      (node (ref "U7") (pin "31") (pinfunction "IO19_31") (pintype "bidirectional"))
    )
    (net (code "60") (name "STAT_LED3") (class "Default")
      (node (ref "R2") (pin "2") (pinfunction "2_2") (pintype "passive"))
      (node (ref "U7") (pin "30") (pinfunction "IO18_30") (pintype "bidirectional"))
    )
    (net (code "61") (name "TXD0") (class "Default")
      (node (ref "R33") (pin "1") (pinfunction "1_1") (pintype "passive"))
      (node (ref "U2") (pin "4") (pinfunction "RXD_4") (pintype "input"))
    )
    (net (code "62") (name "U2RXD") (class "Default")
      (node (ref "R37") (pin "1") (pinfunction "1_1") (pintype "passive"))
      (node (ref "U7") (pin "27") (pinfunction "IO16_27") (pintype "bidirectional"))
    )
    (net (code "63") (name "VCC_RF") (class "Default")
      (node (ref "R5") (pin "1") (pinfunction "1_1") (pintype "passive"))
      (node (ref "U5") (pin "14") (pinfunction "VCC_RF_14") (pintype "power_in"))
    )
    (net (code "64") (name "VOX_RAWA") (class "Default")
      (node (ref "R20") (pin "2") (pinfunction "2_2") (pintype "passive"))
      (node (ref "U8") (pin "5") (pinfunction "5_5") (pintype "bidirectional"))
      (node (ref "U9") (pin "B") (pinfunction "RS1_OX_B") (pintype "bidirectional"))
    )
    (net (code "65") (name "VOX_RAWB") (class "Default")
      (node (ref "U7") (pin "7") (pinfunction "I35/A1_7_7") (pintype "bidirectional"))
      (node (ref "U8") (pin "6") (pinfunction "6_6") (pintype "bidirectional"))
      (node (ref "U8") (pin "7") (pinfunction "7_7") (pintype "bidirectional"))
    )
    (net (code "66") (name "VRED_RAWA") (class "Default")
      (node (ref "R11") (pin "2") (pinfunction "2_2") (pintype "passive"))
      (node (ref "U8") (pin "3") (pinfunction "3_3") (pintype "bidirectional"))
      (node (ref "U9") (pin "D") (pinfunction "RS1_RED_D") (pintype "bidirectional"))
    )
    (net (code "67") (name "VRED_RAWB") (class "Default")
      (node (ref "U7") (pin "6") (pinfunction "I34/A1_6_6") (pintype "bidirectional"))
      (node (ref "U8") (pin "1") (pinfunction "1_1") (pintype "bidirectional"))
      (node (ref "U8") (pin "2") (pinfunction "2_2") (pintype "bidirectional"))
    )
    (net (code "68") (name "unconnected-(SD1-CDN-Pad9)") (class "Default")
      (node (ref "SD1") (pin "9") (pinfunction "CDN_9") (pintype "bidirectional"))
    )
    (net (code "69") (name "unconnected-(U2-ACT#-Pad2)") (class "Default")
      (node (ref "U2") (pin "2") (pinfunction "ACT#_2") (pintype "output"))
    )
    (net (code "70") (name "unconnected-(U2-CKO-Pad1)") (class "Default")
      (node (ref "U2") (pin "1") (pinfunction "CKO_1") (pintype "output"))
    )
    (net (code "71") (name "unconnected-(U2-CTS#-Pad11)") (class "Default")
      (node (ref "U2") (pin "11") (pinfunction "CTS#_11") (pintype "input"))
    )
    (net (code "72") (name "unconnected-(U2-DCD#-Pad14)") (class "Default")
      (node (ref "U2") (pin "14") (pinfunction "DCD#_14") (pintype "input"))
    )
    (net (code "73") (name "unconnected-(U2-DSR#-Pad12)") (class "Default")
      (node (ref "U2") (pin "12") (pinfunction "DSR#_12") (pintype "input"))
    )
    (net (code "74") (name "unconnected-(U2-NC-Pad17)") (class "Default")
      (node (ref "U2") (pin "17") (pinfunction "NC_17") (pintype "no_connect"))
    )
    (net (code "75") (name "unconnected-(U2-R232-Pad18)") (class "Default")
      (node (ref "U2") (pin "18") (pinfunction "R232_18") (pintype "input"))
    )
    (net (code "76") (name "unconnected-(U2-RI#-Pad13)") (class "Default")
      (node (ref "U2") (pin "13") (pinfunction "RI#_13") (pintype "input"))
    )
    (net (code "77") (name "unconnected-(U5-NC-Pad7)") (class "Default")
      (node (ref "U5") (pin "7") (pinfunction "NC_7") (pintype "bidirectional"))
    )
    (net (code "78") (name "unconnected-(U5-NC-Pad15)") (class "Default")
      (node (ref "U5") (pin "15") (pinfunction "NC_15") (pintype "bidirectional"))
    )
    (net (code "79") (name "unconnected-(U5-STANDBY-Pad5)") (class "Default")
      (node (ref "U5") (pin "5") (pinfunction "STANDBY_5") (pintype "bidirectional"))
    )
    (net (code "80") (name "unconnected-(U5-TIMER-Pad18)") (class "Default")
      (node (ref "U5") (pin "18") (pinfunction "TIMER_18") (pintype "bidirectional"))
    )
    (net (code "81") (name "unconnected-(U6-PadRXD)") (class "Default")
      (node (ref "U6") (pin "RXD") (pinfunction "RXD_RXD") (pintype "bidirectional"))
    )
    (net (code "82") (name "unconnected-(U7-CLK-Pad20)") (class "Default")
      (node (ref "U7") (pin "20") (pinfunction "CLK_20") (pintype "bidirectional"))
    )
    (net (code "83") (name "unconnected-(U7-CMD-Pad19)") (class "Default")
      (node (ref "U7") (pin "19") (pinfunction "CMD_19") (pintype "bidirectional"))
    )
    (net (code "84") (name "unconnected-(U7-IO17-Pad28)") (class "Default")
      (node (ref "U7") (pin "28") (pinfunction "IO17_28") (pintype "bidirectional"))
    )
    (net (code "85") (name "unconnected-(U7-SD0-Pad21)") (class "Default")
      (node (ref "U7") (pin "21") (pinfunction "SD0_21") (pintype "bidirectional"))
    )
    (net (code "86") (name "unconnected-(U7-SD1-Pad22)") (class "Default")
      (node (ref "U7") (pin "22") (pinfunction "SD1_22") (pintype "bidirectional"))
    )
    (net (code "87") (name "unconnected-(U7-SD2-Pad17)") (class "Default")
      (node (ref "U7") (pin "17") (pinfunction "SD2_17") (pintype "bidirectional"))
    )
    (net (code "88") (name "unconnected-(U7-SD3-Pad18)") (class "Default")
      (node (ref "U7") (pin "18") (pinfunction "SD3_18") (pintype "bidirectional"))
    )
    (net (code "89") (name "unconnected-(USB1-ID-Pad4)") (class "Default")
      (node (ref "USB1") (pin "4") (pinfunction "ID_4") (pintype "bidirectional"))
    )
  )
)
